# Driver_and_Matrix_PCB_v2.net
KiCad netlist of a schematic drawn in EAGLE
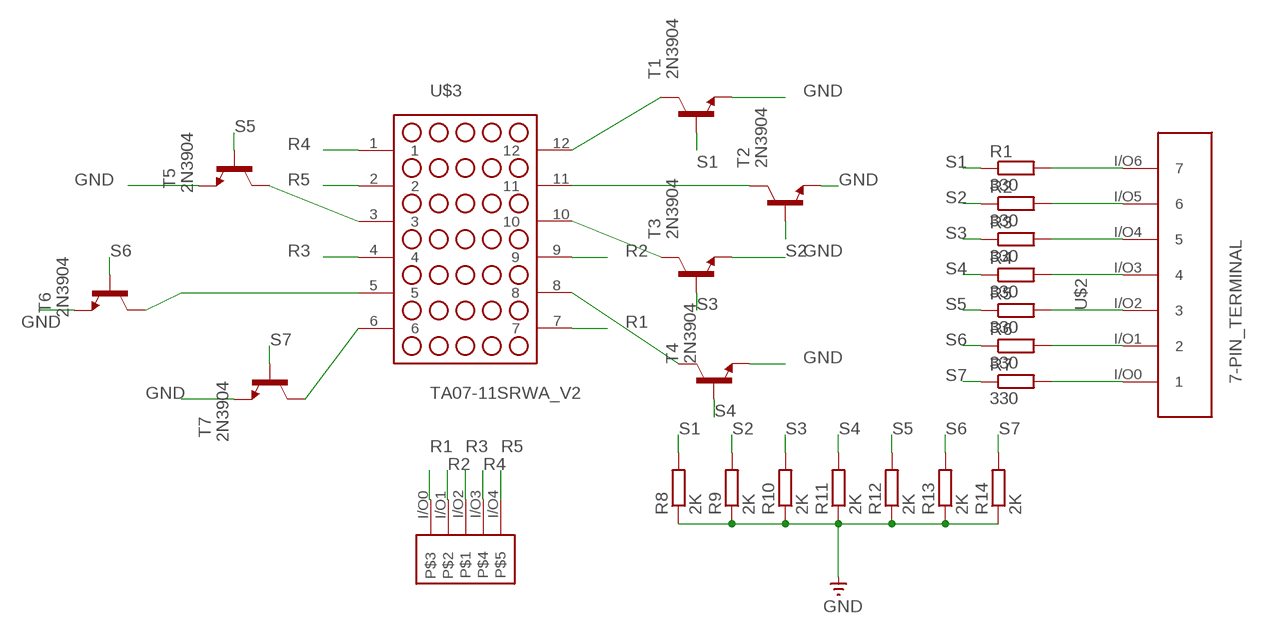
[diagram p0: schematic, sheet 1]

(export (version "E")
  (design (tool "Eeschema 10.0.6"))
  (components
    (comp (ref "GND1")
      (value "GND")
      (footprint "eagle-import:GND")
      (libsource (lib "eagle-import") (part "GND"))
    )
    (comp (ref "R1")
      (value "330")
      (footprint "eagle-import:0207_10")
      (libsource (lib "eagle-import") (part "R-EU_0207/10"))
    )
    (comp (ref "R2")
      (value "330")
      (footprint "eagle-import:0207_10")
      (libsource (lib "eagle-import") (part "R-EU_0207/10"))
    )
    (comp (ref "R3")
      (value "330")
      (footprint "eagle-import:0207_10")
      (libsource (lib "eagle-import") (part "R-EU_0207/10"))
    )
    (comp (ref "R4")
      (value "330")
      (footprint "eagle-import:0207_10")
      (libsource (lib "eagle-import") (part "R-EU_0207/10"))
    )
    (comp (ref "R5")
      (value "330")
      (footprint "eagle-import:0207_10")
      (libsource (lib "eagle-import") (part "R-EU_0207/10"))
    )
    (comp (ref "R6")
      (value "330")
      (footprint "eagle-import:0207_10")
      (libsource (lib "eagle-import") (part "R-EU_0207/10"))
    )
    (comp (ref "R7")
      (value "330")
      (footprint "eagle-import:0207_10")
      (libsource (lib "eagle-import") (part "R-EU_0207/10"))
    )
    (comp (ref "R8")
      (value "2K")
      (footprint "eagle-import:0207_12")
      (libsource (lib "eagle-import") (part "R-EU_0207/12"))
    )
    (comp (ref "R9")
      (value "2K")
      (footprint "eagle-import:0207_12")
      (libsource (lib "eagle-import") (part "R-EU_0207/12"))
    )
    (comp (ref "R10")
      (value "2K")
      (footprint "eagle-import:0207_12")
      (libsource (lib "eagle-import") (part "R-EU_0207/12"))
    )
    (comp (ref "R11")
      (value "2K")
      (footprint "eagle-import:0207_12")
      (libsource (lib "eagle-import") (part "R-EU_0207/12"))
    )
    (comp (ref "R12")
      (value "2K")
      (footprint "eagle-import:0207_12")
      (libsource (lib "eagle-import") (part "R-EU_0207/12"))
    )
    (comp (ref "R13")
      (value "2K")
      (footprint "eagle-import:0207_12")
      (libsource (lib "eagle-import") (part "R-EU_0207/12"))
    )
    (comp (ref "R14")
      (value "2K")
      (footprint "eagle-import:0207_12")
      (libsource (lib "eagle-import") (part "R-EU_0207/12"))
    )
    (comp (ref "T1")
      (value "2N3904")
      (footprint "eagle-import:TO92")
      (libsource (lib "eagle-import") (part "2N3904"))
    )
    (comp (ref "T2")
      (value "2N3904")
      (footprint "eagle-import:TO92")
      (libsource (lib "eagle-import") (part "2N3904"))
    )
    (comp (ref "T3")
      (value "2N3904")
      (footprint "eagle-import:TO92")
      (libsource (lib "eagle-import") (part "2N3904"))
    )
    (comp (ref "T4")
      (value "2N3904")
      (footprint "eagle-import:TO92")
      (libsource (lib "eagle-import") (part "2N3904"))
    )
    (comp (ref "T5")
      (value "2N3904")
      (footprint "eagle-import:TO92")
      (libsource (lib "eagle-import") (part "2N3904"))
    )
    (comp (ref "T6")
      (value "2N3904")
      (footprint "eagle-import:TO92")
      (libsource (lib "eagle-import") (part "2N3904"))
    )
    (comp (ref "T7")
      (value "2N3904")
      (footprint "eagle-import:TO92")
      (libsource (lib "eagle-import") (part "2N3904"))
    )
    (comp (ref "U$1")
      (value "5-PIN_TERMINAL")
      (footprint "eagle-import:5-PIN_TERMINAL")
      (libsource (lib "eagle-import") (part "5-PIN_TERMINAL"))
    )
    (comp (ref "U$2")
      (value "7-PIN_TERMINAL")
      (footprint "eagle-import:7-PIN_TERMINAL")
      (libsource (lib "eagle-import") (part "7-PIN_TERMINAL"))
    )
    (comp (ref "U$3")
      (value "TA07-11SRWA_V2")
      (footprint "eagle-import:TA07-11SRWA_V2")
      (libsource (lib "eagle-import") (part "TA07-11SRWA_V2"))
    )
  )
  (nets
    (net (code "1") (name "/R1") (class "Default")
      (node (ref "U$1") (pin "I/O0") (pinfunction "P$3_I/O0") (pintype "bidirectional"))
      (node (ref "U$3") (pin "7") (pinfunction "7_7") (pintype "bidirectional"))
    )
    (net (code "2") (name "/R2") (class "Default")
      (node (ref "U$1") (pin "I/O1") (pinfunction "P$2_I/O1") (pintype "bidirectional"))
      (node (ref "U$3") (pin "9") (pinfunction "9_9") (pintype "bidirectional"))
    )
    (net (code "3") (name "/R3") (class "Default")
      (node (ref "U$1") (pin "I/O2") (pinfunction "P$1_I/O2") (pintype "bidirectional"))
      (node (ref "U$3") (pin "4") (pinfunction "4_4") (pintype "bidirectional"))
    )
    (net (code "4") (name "/R4") (class "Default")
      (node (ref "U$1") (pin "I/O3") (pinfunction "P$4_I/O3") (pintype "bidirectional"))
      (node (ref "U$3") (pin "1") (pinfunction "1_1") (pintype "bidirectional"))
    )
    (net (code "5") (name "/R5") (class "Default")
      (node (ref "U$1") (pin "I/O4") (pinfunction "P$5_I/O4") (pintype "bidirectional"))
      (node (ref "U$3") (pin "2") (pinfunction "2_2") (pintype "bidirectional"))
    )
    (net (code "6") (name "/S1") (class "Default")
      (node (ref "R1") (pin "1") (pinfunction "1_1") (pintype "passive"))
      (node (ref "R8") (pin "2") (pinfunction "2_2") (pintype "passive"))
      (node (ref "T1") (pin "2") (pinfunction "B_2") (pintype "passive"))
    )
    (net (code "7") (name "/S2") (class "Default")
      (node (ref "R2") (pin "1") (pinfunction "1_1") (pintype "passive"))
      (node (ref "R9") (pin "2") (pinfunction "2_2") (pintype "passive"))
      (node (ref "T2") (pin "2") (pinfunction "B_2") (pintype "passive"))
    )
    (net (code "8") (name "/S3") (class "Default")
      (node (ref "R10") (pin "2") (pinfunction "2_2") (pintype "passive"))
      (node (ref "R3") (pin "1") (pinfunction "1_1") (pintype "passive"))
      (node (ref "T3") (pin "2") (pinfunction "B_2") (pintype "passive"))
    )
    (net (code "9") (name "/S4") (class "Default")
      (node (ref "R11") (pin "2") (pinfunction "2_2") (pintype "passive"))
      (node (ref "R4") (pin "1") (pinfunction "1_1") (pintype "passive"))
      (node (ref "T4") (pin "2") (pinfunction "B_2") (pintype "passive"))
    )
    (net (code "10") (name "/S5") (class "Default")
      (node (ref "R12") (pin "2") (pinfunction "2_2") (pintype "passive"))
      (node (ref "R5") (pin "1") (pinfunction "1_1") (pintype "passive"))
      (node (ref "T5") (pin "2") (pinfunction "B_2") (pintype "passive"))
    )
    (net (code "11") (name "/S6") (class "Default")
      (node (ref "R13") (pin "2") (pinfunction "2_2") (pintype "passive"))
      (node (ref "R6") (pin "1") (pinfunction "1_1") (pintype "passive"))
      (node (ref "T6") (pin "2") (pinfunction "B_2") (pintype "passive"))
    )
    (net (code "12") (name "/S7") (class "Default")
      (node (ref "R14") (pin "2") (pinfunction "2_2") (pintype "passive"))
      (node (ref "R7") (pin "1") (pinfunction "1_1") (pintype "passive"))
      (node (ref "T7") (pin "2") (pinfunction "B_2") (pintype "passive"))
    )
    (net (code "13") (name "GND") (class "Default")
      (node (ref "GND1") (pin "P$1") (pinfunction "GND_P$1") (pintype "power_in"))
      (node (ref "R10") (pin "1") (pinfunction "1_1") (pintype "passive"))
      (node (ref "R11") (pin "1") (pinfunction "1_1") (pintype "passive"))
      (node (ref "R12") (pin "1") (pinfunction "1_1") (pintype "passive"))
      (node (ref "R13") (pin "1") (pinfunction "1_1") (pintype "passive"))
      (node (ref "R14") (pin "1") (pinfunction "1_1") (pintype "passive"))
      (node (ref "R8") (pin "1") (pinfunction "1_1") (pintype "passive"))
      (node (ref "R9") (pin "1") (pinfunction "1_1") (pintype "passive"))
      (node (ref "T1") (pin "3") (pinfunction "E_3") (pintype "passive"))
      (node (ref "T2") (pin "3") (pinfunction "E_3") (pintype "passive"))
      (node (ref "T3") (pin "3") (pinfunction "E_3") (pintype "passive"))
      (node (ref "T4") (pin "3") (pinfunction "E_3") (pintype "passive"))
      (node (ref "T5") (pin "3") (pinfunction "E_3") (pintype "passive"))
      (node (ref "T6") (pin "3") (pinfunction "E_3") (pintype "passive"))
      (node (ref "T7") (pin "3") (pinfunction "E_3") (pintype "passive"))
    )
    (net (code "14") (name "Net-(T1-C)") (class "Default")
      (node (ref "T1") (pin "1") (pinfunction "C_1") (pintype "passive"))
      (node (ref "U$3") (pin "12") (pinfunction "12_12") (pintype "bidirectional"))
    )
    (net (code "15") (name "Net-(T2-C)") (class "Default")
      (node (ref "T2") (pin "1") (pinfunction "C_1") (pintype "passive"))
      (node (ref "U$3") (pin "11") (pinfunction "11_11") (pintype "bidirectional"))
    )
    (net (code "16") (name "Net-(T3-C)") (class "Default")
      (node (ref "T3") (pin "1") (pinfunction "C_1") (pintype "passive"))
      (node (ref "U$3") (pin "10") (pinfunction "10_10") (pintype "bidirectional"))
    )
    (net (code "17") (name "Net-(T4-C)") (class "Default")
      (node (ref "T4") (pin "1") (pinfunction "C_1") (pintype "passive"))
      (node (ref "U$3") (pin "8") (pinfunction "8_8") (pintype "bidirectional"))
    )
    (net (code "18") (name "Net-(T5-C)") (class "Default")
      (node (ref "T5") (pin "1") (pinfunction "C_1") (pintype "passive"))
      (node (ref "U$3") (pin "3") (pinfunction "3_3") (pintype "bidirectional"))
    )
    (net (code "19") (name "Net-(T6-C)") (class "Default")
      (node (ref "T6") (pin "1") (pinfunction "C_1") (pintype "passive"))
      (node (ref "U$3") (pin "5") (pinfunction "5_5") (pintype "bidirectional"))
    )
    (net (code "20") (name "Net-(T7-C)") (class "Default")
      (node (ref "T7") (pin "1") (pinfunction "C_1") (pintype "passive"))
      (node (ref "U$3") (pin "6") (pinfunction "6_6") (pintype "bidirectional"))
    )
    (net (code "21") (name "Net-(U$2-1)") (class "Default")
      (node (ref "R7") (pin "2") (pinfunction "2_2") (pintype "passive"))
      (node (ref "U$2") (pin "I/O0") (pinfunction "1_I/O0") (pintype "bidirectional"))
    )
    (net (code "22") (name "Net-(U$2-2)") (class "Default")
      (node (ref "R6") (pin "2") (pinfunction "2_2") (pintype "passive"))
      (node (ref "U$2") (pin "I/O1") (pinfunction "2_I/O1") (pintype "bidirectional"))
    )
    (net (code "23") (name "Net-(U$2-3)") (class "Default")
      (node (ref "R5") (pin "2") (pinfunction "2_2") (pintype "passive"))
      (node (ref "U$2") (pin "I/O2") (pinfunction "3_I/O2") (pintype "bidirectional"))
    )
    (net (code "24") (name "Net-(U$2-4)") (class "Default")
      (node (ref "R4") (pin "2") (pinfunction "2_2") (pintype "passive"))
      (node (ref "U$2") (pin "I/O3") (pinfunction "4_I/O3") (pintype "bidirectional"))
    )
    (net (code "25") (name "Net-(U$2-5)") (class "Default")
      (node (ref "R3") (pin "2") (pinfunction "2_2") (pintype "passive"))
      (node (ref "U$2") (pin "I/O4") (pinfunction "5_I/O4") (pintype "bidirectional"))
    )
    (net (code "26") (name "Net-(U$2-6)") (class "Default")
      (node (ref "R2") (pin "2") (pinfunction "2_2") (pintype "passive"))
      (node (ref "U$2") (pin "I/O5") (pinfunction "6_I/O5") (pintype "bidirectional"))
    )
    (net (code "27") (name "Net-(U$2-7)") (class "Default")
      (node (ref "R1") (pin "2") (pinfunction "2_2") (pintype "passive"))
      (node (ref "U$2") (pin "I/O6") (pinfunction "7_I/O6") (pintype "bidirectional"))
    )
  )
)
